# Scoreboard_Wifi_Controller_20170423.net
KiCad netlist of a schematic drawn in EAGLE
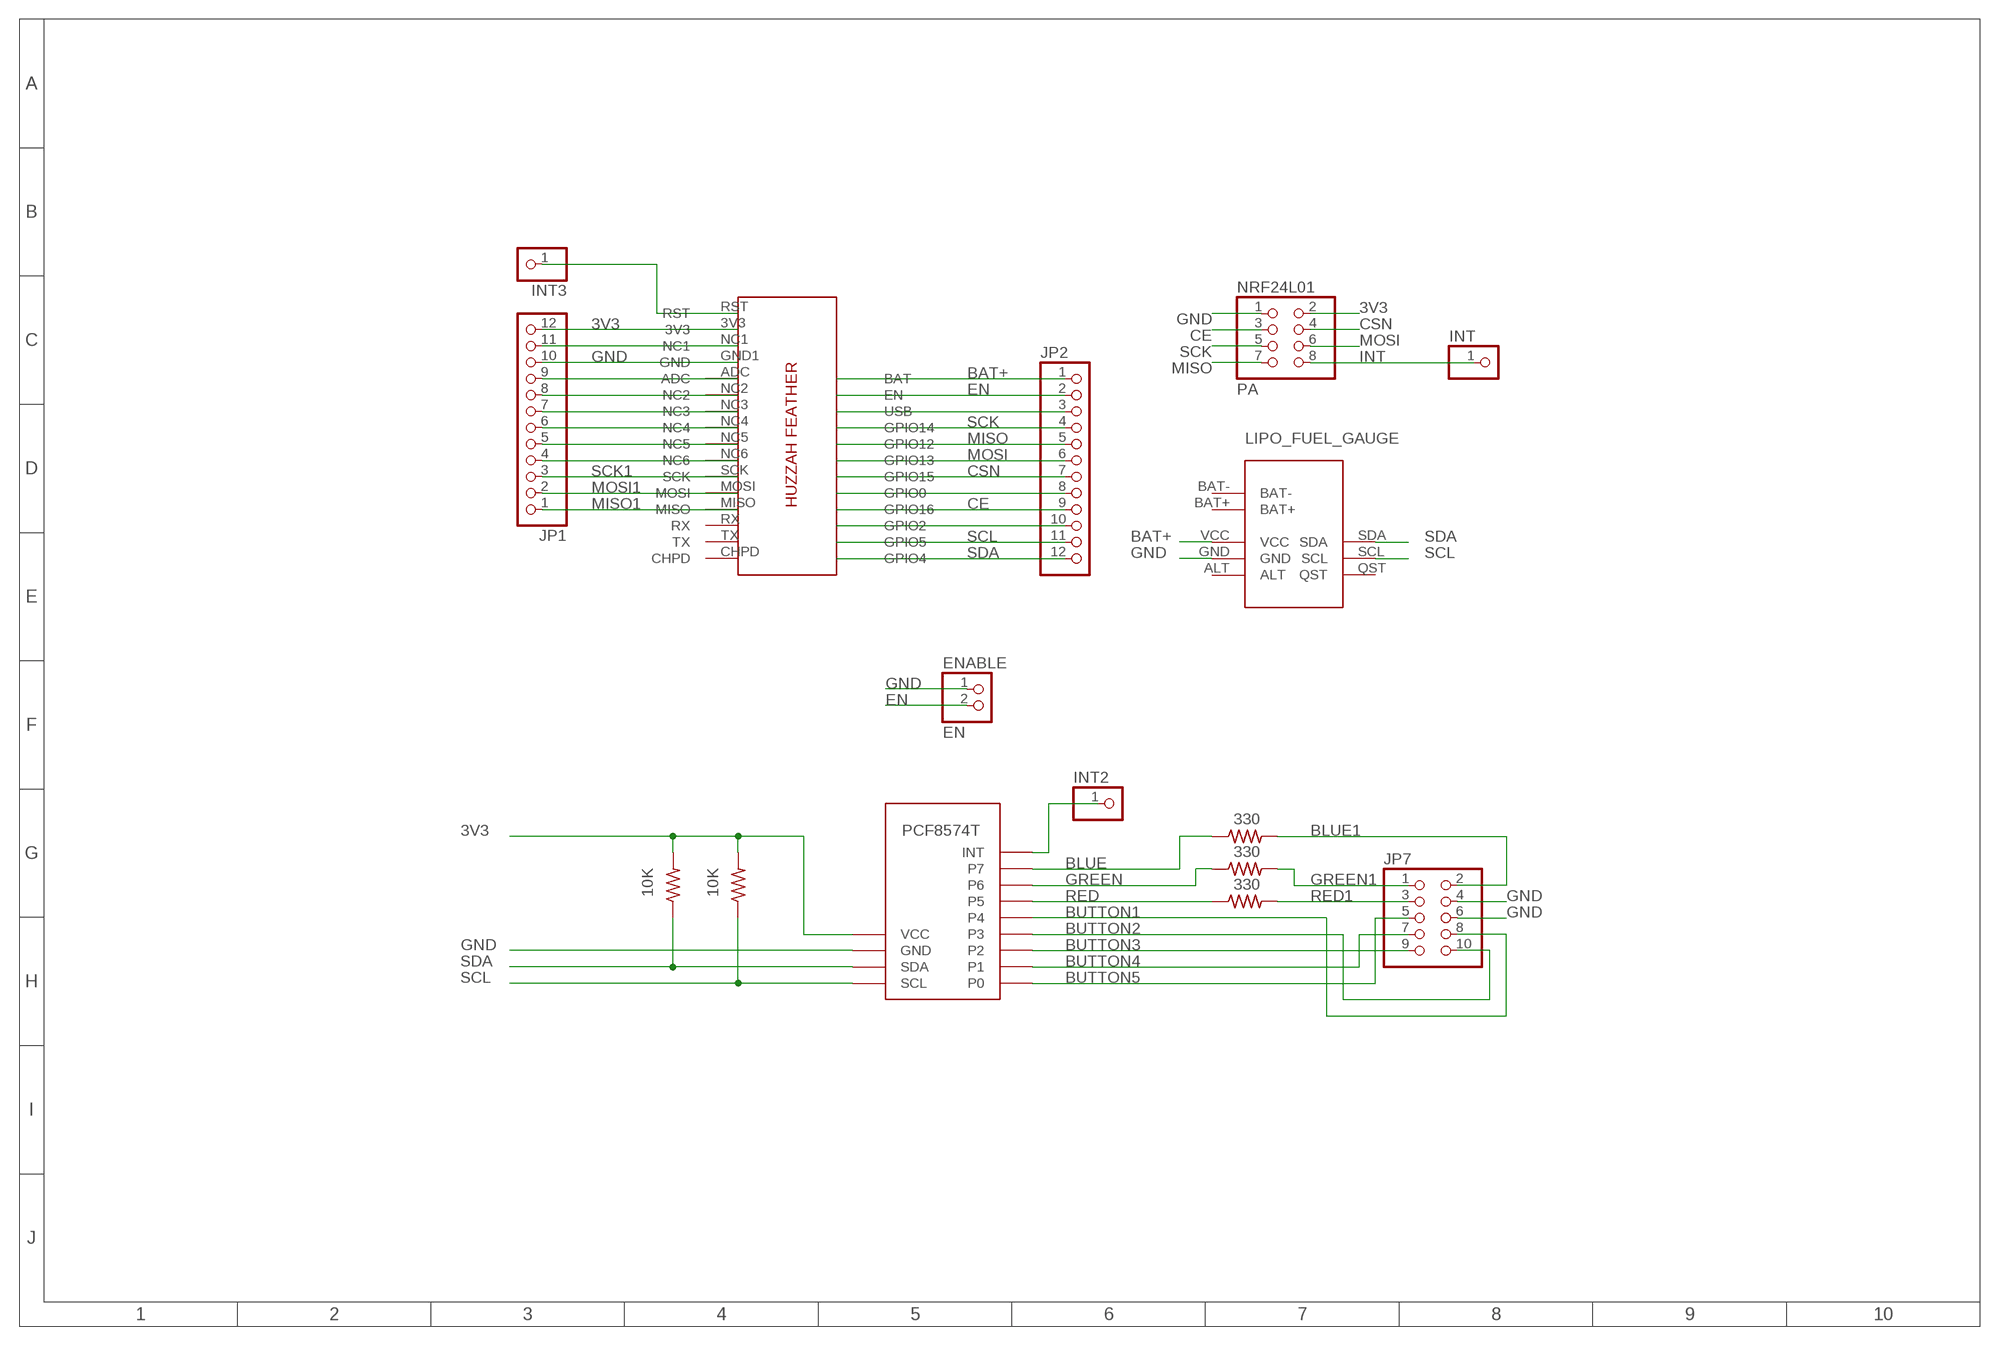
[diagram p0: schematic, sheet 1]

(export (version "E")
  (design (tool "Eeschema 10.0.6"))
  (components
    (comp (ref "ENABLE")
      (value "EN")
      (footprint "eagle-import:1X02_90")
      (libsource (lib "eagle-import") (part "PINHD-1X2/90"))
    )
    (comp (ref "INT")
      (value "PINHD-1X1CB")
      (footprint "eagle-import:1X01-CLEANBIG")
      (libsource (lib "eagle-import") (part "PINHD-1X1CB"))
    )
    (comp (ref "INT2")
      (value "PINHD-1X1CB")
      (footprint "eagle-import:1X01-CLEANBIG")
      (libsource (lib "eagle-import") (part "PINHD-1X1CB"))
    )
    (comp (ref "INT3")
      (value "PINHD-1X1CB")
      (footprint "eagle-import:1X01-CLEANBIG")
      (libsource (lib "eagle-import") (part "PINHD-1X1CB"))
    )
    (comp (ref "JP1")
      (value "PINHD-1X12-CB")
      (footprint "eagle-import:1X12-CB")
      (libsource (lib "eagle-import") (part "PINHD-1X12-CB"))
    )
    (comp (ref "JP2")
      (value "PINHD-1X12-CB")
      (footprint "eagle-import:1X12-CB")
      (libsource (lib "eagle-import") (part "PINHD-1X12-CB"))
    )
    (comp (ref "JP7")
      (value "PINHD-2X5/90")
      (footprint "eagle-import:2X05_90")
      (libsource (lib "eagle-import") (part "PINHD-2X5/90"))
    )
    (comp (ref "LIPO_FUEL_GAUGE")
      (value "LIPO_FUEL_GAUGE")
      (footprint "eagle-import:LIPO_FUEL_GAUGE")
      (libsource (lib "eagle-import") (part "LIPO_FUEL_GAUGE"))
    )
    (comp (ref "NRF24L01")
      (value "PA")
      (footprint "eagle-import:2X04_90")
      (libsource (lib "eagle-import") (part "PINHD-2X4/90"))
    )
    (comp (ref "R2")
      (value "330")
      (footprint "eagle-import:0207_10")
      (libsource (lib "eagle-import") (part "R-US_0207/10"))
    )
    (comp (ref "R3")
      (value "330")
      (footprint "eagle-import:0207_10")
      (libsource (lib "eagle-import") (part "R-US_0207/10"))
    )
    (comp (ref "R4")
      (value "330")
      (footprint "eagle-import:0207_10")
      (libsource (lib "eagle-import") (part "R-US_0207/10"))
    )
    (comp (ref "R5")
      (value "10K")
      (footprint "eagle-import:0207_10")
      (libsource (lib "eagle-import") (part "R-US_0207/10"))
    )
    (comp (ref "R6")
      (value "10K")
      (footprint "eagle-import:0207_10")
      (libsource (lib "eagle-import") (part "R-US_0207/10"))
    )
    (comp (ref "U$1")
      (value "ADAFRUIT-FEATHER-ESP8266-HUZZAHALT")
      (footprint "eagle-import:ADAFRUIT-FEATHER-ESP8266-HUZZAH-ALT")
      (libsource (lib "eagle-import") (part "ADAFRUIT-FEATHER-ESP8266-HUZZAHALT"))
    )
    (comp (ref "U$3")
      (value "PCF8574T_IO_EXPANDER")
      (footprint "eagle-import:PCF8574T_IO_EXPANDER")
      (libsource (lib "eagle-import") (part "PCF8574T_IO_EXPANDER"))
    )
  )
  (nets
    (net (code "1") (name "/3V3") (class "Default")
      (node (ref "JP1") (pin "12") (pinfunction "12_12") (pintype "passive"))
      (node (ref "NRF24L01") (pin "2") (pinfunction "2_2") (pintype "passive"))
      (node (ref "R5") (pin "2") (pinfunction "2_2") (pintype "passive"))
      (node (ref "R6") (pin "2") (pinfunction "2_2") (pintype "passive"))
      (node (ref "U$1") (pin "3V3") (pinfunction "3V3_3V3") (pintype "bidirectional"))
      (node (ref "U$3") (pin "VCC") (pinfunction "VCC_VCC") (pintype "input"))
    )
    (net (code "2") (name "/BAT+") (class "Default")
      (node (ref "JP2") (pin "1") (pinfunction "1_1") (pintype "passive"))
      (node (ref "LIPO_FUEL_GAUGE") (pin "VCC") (pinfunction "VCC_VCC") (pintype "bidirectional"))
      (node (ref "U$1") (pin "BAT") (pinfunction "BAT_BAT") (pintype "bidirectional"))
    )
    (net (code "3") (name "/BLUE") (class "Default")
      (node (ref "R2") (pin "1") (pinfunction "1_1") (pintype "passive"))
      (node (ref "U$3") (pin "P$7") (pinfunction "P7_P$7") (pintype "bidirectional"))
    )
    (net (code "4") (name "/BLUE1") (class "Default")
      (node (ref "JP7") (pin "2") (pinfunction "2_2") (pintype "passive"))
      (node (ref "R2") (pin "2") (pinfunction "2_2") (pintype "passive"))
    )
    (net (code "5") (name "/BUTTON1") (class "Default")
      (node (ref "JP7") (pin "8") (pinfunction "8_8") (pintype "passive"))
      (node (ref "U$3") (pin "P$4") (pinfunction "P4_P$4") (pintype "bidirectional"))
    )
    (net (code "6") (name "/BUTTON2") (class "Default")
      (node (ref "JP7") (pin "10") (pinfunction "10_10") (pintype "passive"))
      (node (ref "U$3") (pin "P$3") (pinfunction "P3_P$3") (pintype "bidirectional"))
    )
    (net (code "7") (name "/BUTTON3") (class "Default")
      (node (ref "JP7") (pin "9") (pinfunction "9_9") (pintype "passive"))
      (node (ref "U$3") (pin "P$2") (pinfunction "P2_P$2") (pintype "bidirectional"))
    )
    (net (code "8") (name "/BUTTON4") (class "Default")
      (node (ref "JP7") (pin "7") (pinfunction "7_7") (pintype "passive"))
      (node (ref "U$3") (pin "P$1") (pinfunction "P1_P$1") (pintype "bidirectional"))
    )
    (net (code "9") (name "/BUTTON5") (class "Default")
      (node (ref "JP7") (pin "5") (pinfunction "5_5") (pintype "passive"))
      (node (ref "U$3") (pin "P$0") (pinfunction "P0_P$0") (pintype "bidirectional"))
    )
    (net (code "10") (name "/CE") (class "Default")
      (node (ref "JP2") (pin "9") (pinfunction "9_9") (pintype "passive"))
      (node (ref "NRF24L01") (pin "3") (pinfunction "3_3") (pintype "passive"))
      (node (ref "U$1") (pin "GPIO16") (pinfunction "GPIO16_GPIO16") (pintype "bidirectional"))
    )
    (net (code "11") (name "/CSN") (class "Default")
      (node (ref "JP2") (pin "7") (pinfunction "7_7") (pintype "passive"))
      (node (ref "NRF24L01") (pin "4") (pinfunction "4_4") (pintype "passive"))
      (node (ref "U$1") (pin "GPIO15") (pinfunction "GPIO15_GPIO15") (pintype "bidirectional"))
    )
    (net (code "12") (name "/EN") (class "Default")
      (node (ref "ENABLE") (pin "2") (pinfunction "2_2") (pintype "passive"))
      (node (ref "JP2") (pin "2") (pinfunction "2_2") (pintype "passive"))
      (node (ref "U$1") (pin "EN") (pinfunction "EN_EN") (pintype "bidirectional"))
    )
    (net (code "13") (name "/GND") (class "Default")
      (node (ref "ENABLE") (pin "1") (pinfunction "1_1") (pintype "passive"))
      (node (ref "JP1") (pin "10") (pinfunction "10_10") (pintype "passive"))
      (node (ref "JP7") (pin "4") (pinfunction "4_4") (pintype "passive"))
      (node (ref "JP7") (pin "6") (pinfunction "6_6") (pintype "passive"))
      (node (ref "LIPO_FUEL_GAUGE") (pin "GND") (pinfunction "GND_GND") (pintype "bidirectional"))
      (node (ref "NRF24L01") (pin "1") (pinfunction "1_1") (pintype "passive"))
      (node (ref "U$1") (pin "GND1") (pinfunction "GND_GND1") (pintype "bidirectional"))
      (node (ref "U$3") (pin "GND") (pinfunction "GND_GND") (pintype "input"))
    )
    (net (code "14") (name "/GREEN") (class "Default")
      (node (ref "R3") (pin "1") (pinfunction "1_1") (pintype "passive"))
      (node (ref "U$3") (pin "P$6") (pinfunction "P6_P$6") (pintype "bidirectional"))
    )
    (net (code "15") (name "/GREEN1") (class "Default")
      (node (ref "JP7") (pin "1") (pinfunction "1_1") (pintype "passive"))
      (node (ref "R3") (pin "2") (pinfunction "2_2") (pintype "passive"))
    )
    (net (code "16") (name "/INT") (class "Default")
      (node (ref "INT") (pin "1") (pinfunction "1_1") (pintype "passive"))
      (node (ref "NRF24L01") (pin "8") (pinfunction "8_8") (pintype "passive"))
    )
    (net (code "17") (name "/MISO") (class "Default")
      (node (ref "JP2") (pin "5") (pinfunction "5_5") (pintype "passive"))
      (node (ref "NRF24L01") (pin "7") (pinfunction "7_7") (pintype "passive"))
      (node (ref "U$1") (pin "GPIO12") (pinfunction "GPIO12_GPIO12") (pintype "bidirectional"))
    )
    (net (code "18") (name "/MISO1") (class "Default")
      (node (ref "JP1") (pin "1") (pinfunction "1_1") (pintype "passive"))
      (node (ref "U$1") (pin "MISO") (pinfunction "MISO_MISO") (pintype "bidirectional"))
    )
    (net (code "19") (name "/MOSI") (class "Default")
      (node (ref "JP2") (pin "6") (pinfunction "6_6") (pintype "passive"))
      (node (ref "NRF24L01") (pin "6") (pinfunction "6_6") (pintype "passive"))
      (node (ref "U$1") (pin "GPIO13") (pinfunction "GPIO13_GPIO13") (pintype "bidirectional"))
    )
    (net (code "20") (name "/MOSI1") (class "Default")
      (node (ref "JP1") (pin "2") (pinfunction "2_2") (pintype "passive"))
      (node (ref "U$1") (pin "MOSI") (pinfunction "MOSI_MOSI") (pintype "bidirectional"))
    )
    (net (code "21") (name "/RED") (class "Default")
      (node (ref "R4") (pin "1") (pinfunction "1_1") (pintype "passive"))
      (node (ref "U$3") (pin "P$5") (pinfunction "P5_P$5") (pintype "bidirectional"))
    )
    (net (code "22") (name "/RED1") (class "Default")
      (node (ref "JP7") (pin "3") (pinfunction "3_3") (pintype "passive"))
      (node (ref "R4") (pin "2") (pinfunction "2_2") (pintype "passive"))
    )
    (net (code "23") (name "/SCK") (class "Default")
      (node (ref "JP2") (pin "4") (pinfunction "4_4") (pintype "passive"))
      (node (ref "NRF24L01") (pin "5") (pinfunction "5_5") (pintype "passive"))
      (node (ref "U$1") (pin "GPIO14") (pinfunction "GPIO14_GPIO14") (pintype "bidirectional"))
    )
    (net (code "24") (name "/SCK1") (class "Default")
      (node (ref "JP1") (pin "3") (pinfunction "3_3") (pintype "passive"))
      (node (ref "U$1") (pin "SCK") (pinfunction "SCK_SCK") (pintype "bidirectional"))
    )
    (net (code "25") (name "/SCL") (class "Default")
      (node (ref "JP2") (pin "11") (pinfunction "11_11") (pintype "passive"))
      (node (ref "LIPO_FUEL_GAUGE") (pin "SCL") (pinfunction "SCL_SCL") (pintype "bidirectional"))
      (node (ref "R5") (pin "1") (pinfunction "1_1") (pintype "passive"))
      (node (ref "U$1") (pin "GPIO5") (pinfunction "GPIO5_GPIO5") (pintype "bidirectional"))
      (node (ref "U$3") (pin "SCL") (pinfunction "SCL_SCL") (pintype "bidirectional"))
    )
    (net (code "26") (name "/SDA") (class "Default")
      (node (ref "JP2") (pin "12") (pinfunction "12_12") (pintype "passive"))
      (node (ref "LIPO_FUEL_GAUGE") (pin "SDA") (pinfunction "SDA_SDA") (pintype "bidirectional"))
      (node (ref "R6") (pin "1") (pinfunction "1_1") (pintype "passive"))
      (node (ref "U$1") (pin "GPIO4") (pinfunction "GPIO4_GPIO4") (pintype "bidirectional"))
      (node (ref "U$3") (pin "SDA") (pinfunction "SDA_SDA") (pintype "bidirectional"))
    )
    (net (code "27") (name "Net-(INT2-Pad1)") (class "Default")
      (node (ref "INT2") (pin "1") (pinfunction "1_1") (pintype "passive"))
      (node (ref "U$3") (pin "INT") (pinfunction "INT_INT") (pintype "bidirectional"))
    )
    (net (code "28") (name "Net-(INT3-Pad1)") (class "Default")
      (node (ref "INT3") (pin "1") (pinfunction "1_1") (pintype "passive"))
      (node (ref "U$1") (pin "RST") (pinfunction "RST_RST") (pintype "bidirectional"))
    )
    (net (code "29") (name "Net-(JP1-Pad4)") (class "Default")
      (node (ref "JP1") (pin "4") (pinfunction "4_4") (pintype "passive"))
      (node (ref "U$1") (pin "NC6") (pinfunction "NC6_NC6") (pintype "bidirectional"))
    )
    (net (code "30") (name "Net-(JP1-Pad5)") (class "Default")
      (node (ref "JP1") (pin "5") (pinfunction "5_5") (pintype "passive"))
      (node (ref "U$1") (pin "NC5") (pinfunction "NC5_NC5") (pintype "bidirectional"))
    )
    (net (code "31") (name "Net-(JP1-Pad6)") (class "Default")
      (node (ref "JP1") (pin "6") (pinfunction "6_6") (pintype "passive"))
      (node (ref "U$1") (pin "NC4") (pinfunction "NC4_NC4") (pintype "bidirectional"))
    )
    (net (code "32") (name "Net-(JP1-Pad7)") (class "Default")
      (node (ref "JP1") (pin "7") (pinfunction "7_7") (pintype "passive"))
      (node (ref "U$1") (pin "NC3") (pinfunction "NC3_NC3") (pintype "bidirectional"))
    )
    (net (code "33") (name "Net-(JP1-Pad8)") (class "Default")
      (node (ref "JP1") (pin "8") (pinfunction "8_8") (pintype "passive"))
      (node (ref "U$1") (pin "NC2") (pinfunction "NC2_NC2") (pintype "bidirectional"))
    )
    (net (code "34") (name "Net-(JP1-Pad9)") (class "Default")
      (node (ref "JP1") (pin "9") (pinfunction "9_9") (pintype "passive"))
      (node (ref "U$1") (pin "ADC") (pinfunction "ADC_ADC") (pintype "bidirectional"))
    )
    (net (code "35") (name "Net-(JP1-Pad11)") (class "Default")
      (node (ref "JP1") (pin "11") (pinfunction "11_11") (pintype "passive"))
      (node (ref "U$1") (pin "NC1") (pinfunction "NC1_NC1") (pintype "bidirectional"))
    )
    (net (code "36") (name "Net-(JP2-Pad3)") (class "Default")
      (node (ref "JP2") (pin "3") (pinfunction "3_3") (pintype "passive"))
      (node (ref "U$1") (pin "USB") (pinfunction "USB_USB") (pintype "bidirectional"))
    )
    (net (code "37") (name "Net-(JP2-Pad8)") (class "Default")
      (node (ref "JP2") (pin "8") (pinfunction "8_8") (pintype "passive"))
      (node (ref "U$1") (pin "GPIO0") (pinfunction "GPIO0_GPIO0") (pintype "bidirectional"))
    )
    (net (code "38") (name "Net-(JP2-Pad10)") (class "Default")
      (node (ref "JP2") (pin "10") (pinfunction "10_10") (pintype "passive"))
      (node (ref "U$1") (pin "GPIO2") (pinfunction "GPIO2_GPIO2") (pintype "bidirectional"))
    )
    (net (code "39") (name "unconnected-(LIPO_FUEL_GAUGE-PadALT)") (class "Default")
      (node (ref "LIPO_FUEL_GAUGE") (pin "ALT") (pinfunction "ALT_ALT") (pintype "bidirectional"))
    )
    (net (code "40") (name "unconnected-(LIPO_FUEL_GAUGE-PadBAT+)") (class "Default")
      (node (ref "LIPO_FUEL_GAUGE") (pin "BAT+") (pinfunction "BAT+_BAT+") (pintype "bidirectional"))
    )
    (net (code "41") (name "unconnected-(LIPO_FUEL_GAUGE-PadBAT-)") (class "Default")
      (node (ref "LIPO_FUEL_GAUGE") (pin "BAT-") (pinfunction "BAT-_BAT-") (pintype "bidirectional"))
    )
    (net (code "42") (name "unconnected-(LIPO_FUEL_GAUGE-PadQST)") (class "Default")
      (node (ref "LIPO_FUEL_GAUGE") (pin "QST") (pinfunction "QST_QST") (pintype "bidirectional"))
    )
    (net (code "43") (name "unconnected-(U$1-PadCHPD)") (class "Default")
      (node (ref "U$1") (pin "CHPD") (pinfunction "CHPD_CHPD") (pintype "bidirectional"))
    )
    (net (code "44") (name "unconnected-(U$1-PadRX)") (class "Default")
      (node (ref "U$1") (pin "RX") (pinfunction "RX_RX") (pintype "bidirectional"))
    )
    (net (code "45") (name "unconnected-(U$1-PadTX)") (class "Default")
      (node (ref "U$1") (pin "TX") (pinfunction "TX_TX") (pintype "bidirectional"))
    )
  )
)
